# SCH_USB-hub_2025-08-26.net
KiCad netlist of a schematic drawn in EasyEDA
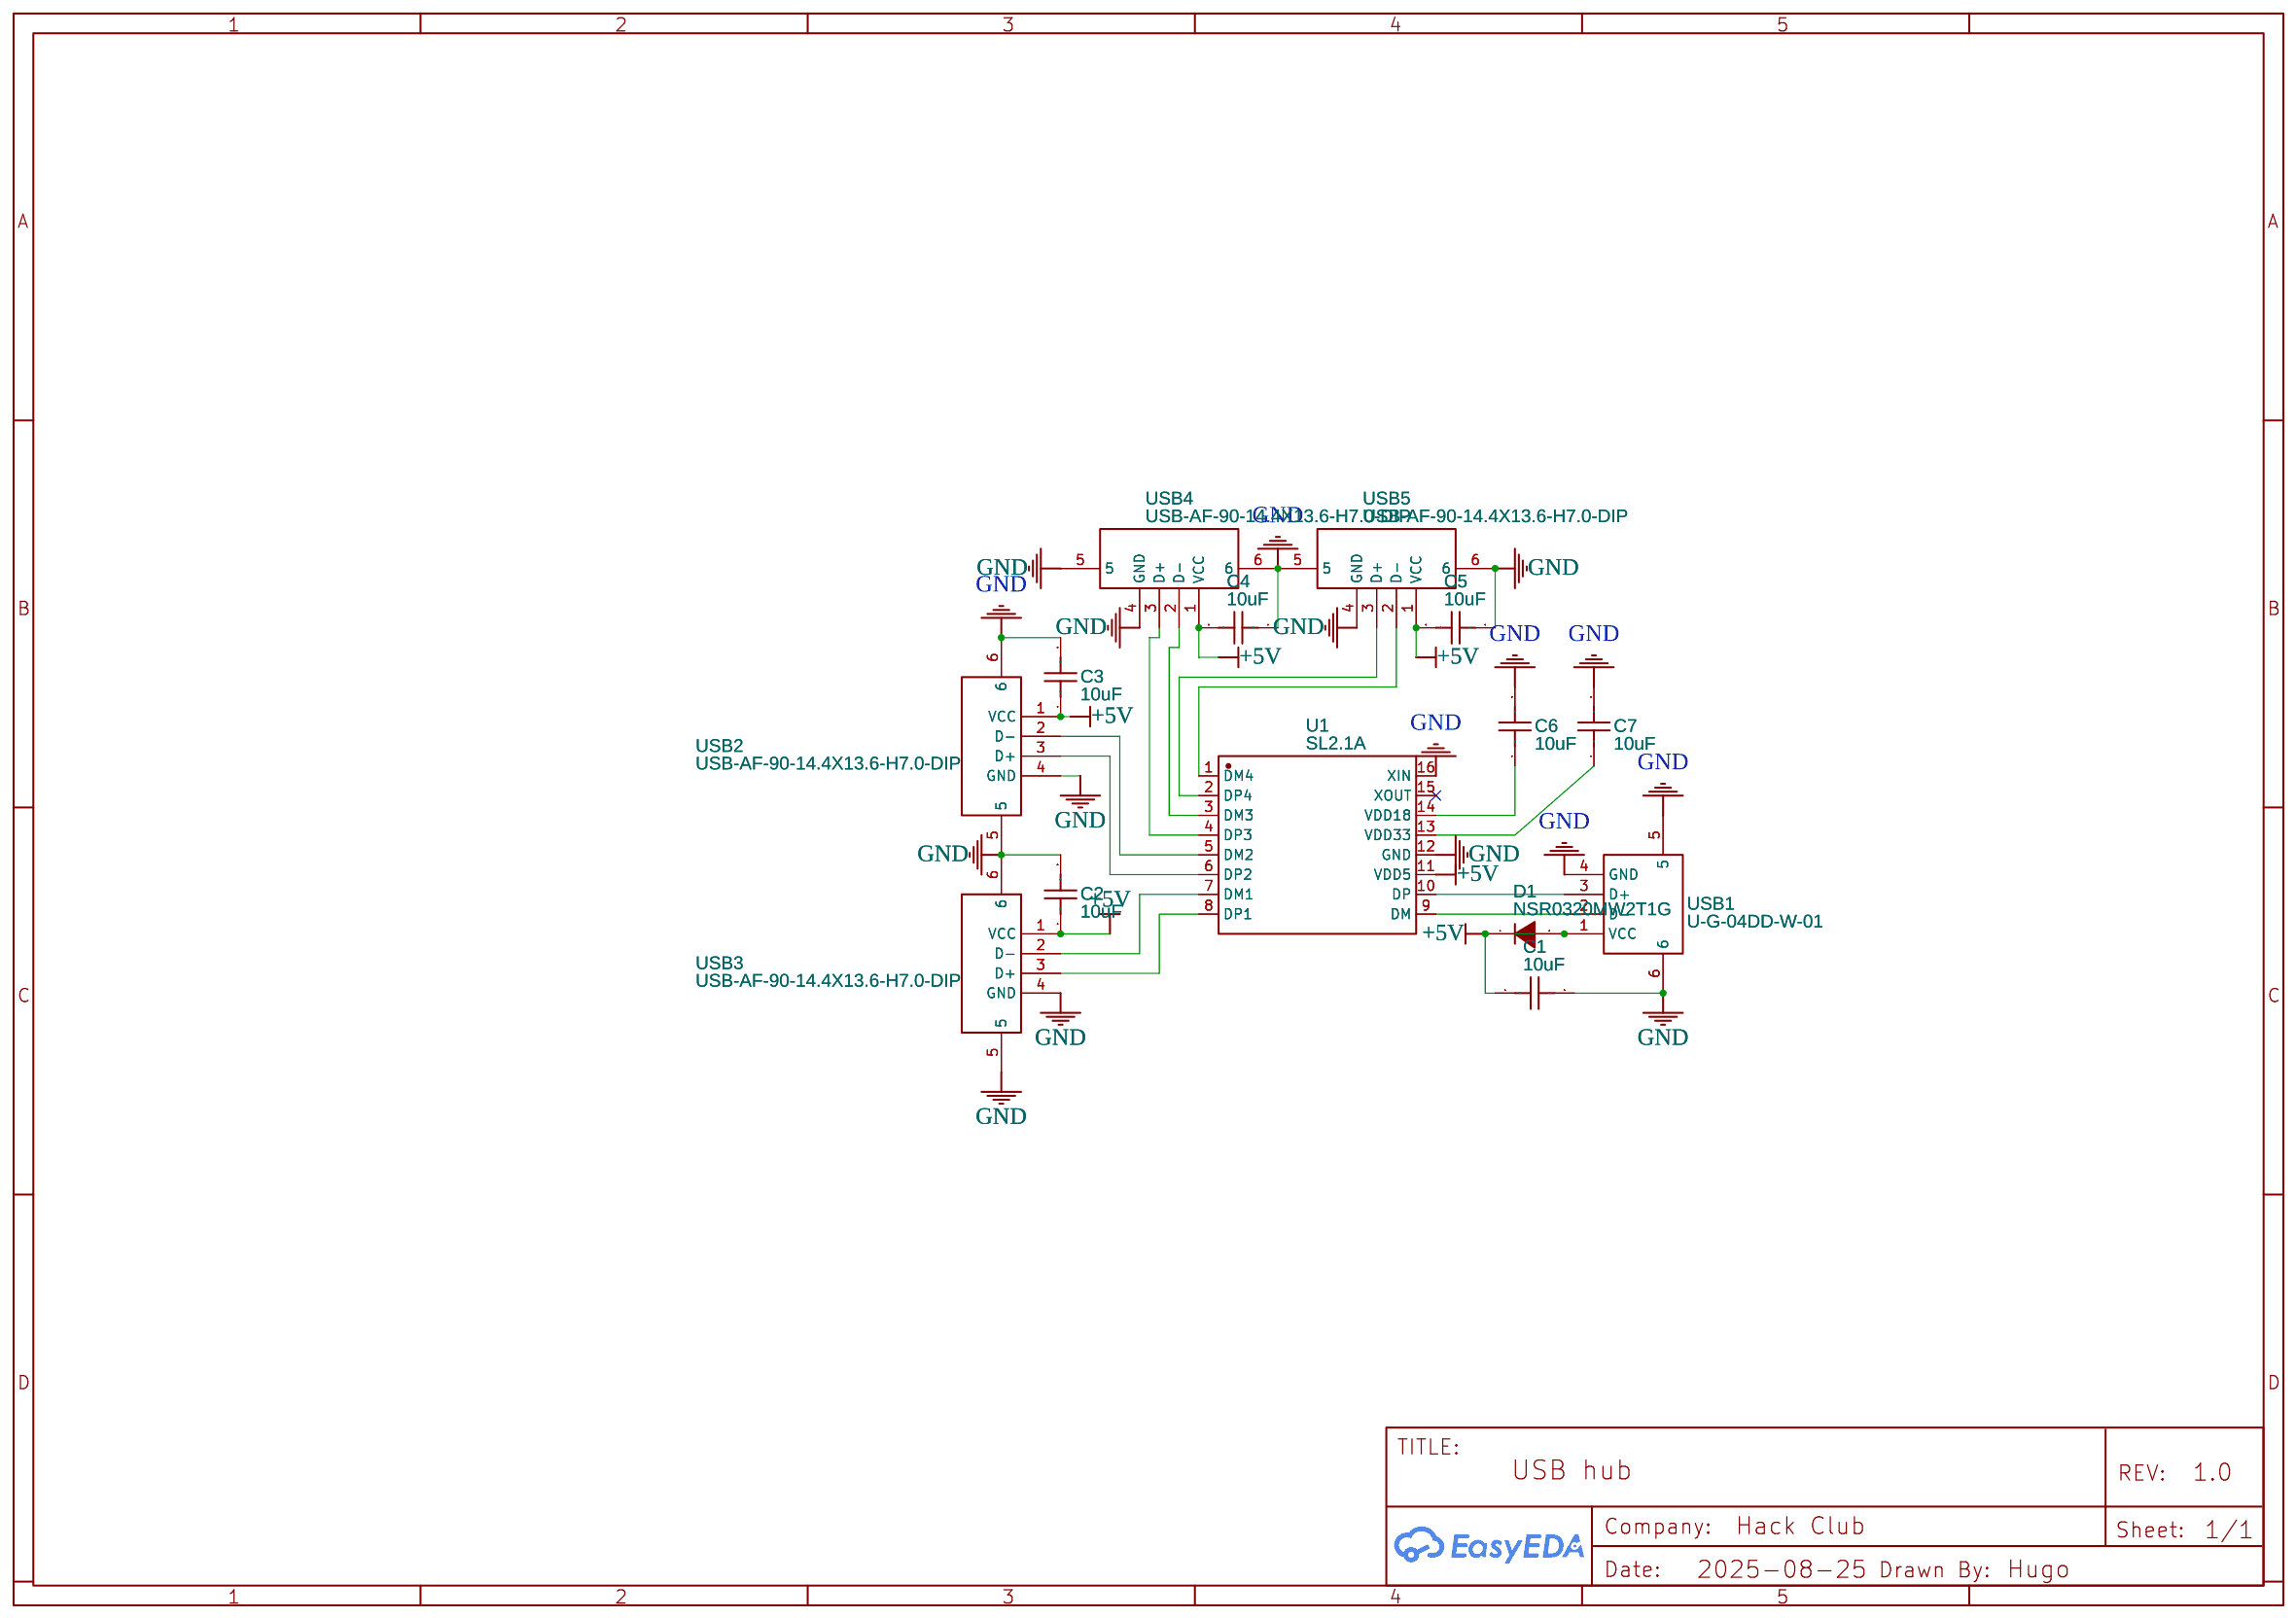
[diagram p0: schematic sheet]

(export (version "E")
  (design (tool "Eeschema 10.0.6"))
  (components
    (comp (ref "C1")
      (value "10uF")
      (fields
        (field (name "Manufacturer Part") "CL10A106KP8NNNC")
        (field (name "Manufacturer") "SAMSUNG(三星)")
      )
      (libsource (lib "") (part "CL10A106KP8NNNC_2"))
    )
    (comp (ref "C2")
      (value "10uF")
      (fields
        (field (name "Manufacturer Part") "CL10A106KP8NNNC")
        (field (name "Manufacturer") "SAMSUNG(三星)")
      )
      (libsource (lib "") (part "CL10A106KP8NNNC"))
    )
    (comp (ref "C3")
      (value "10uF")
      (fields
        (field (name "Manufacturer Part") "CL10A106KP8NNNC")
        (field (name "Manufacturer") "SAMSUNG(三星)")
      )
      (libsource (lib "") (part "CL10A106KP8NNNC"))
    )
    (comp (ref "C4")
      (value "10uF")
      (fields
        (field (name "Manufacturer Part") "CL10A106KP8NNNC")
        (field (name "Manufacturer") "SAMSUNG(三星)")
      )
      (libsource (lib "") (part "CL10A106KP8NNNC_1"))
    )
    (comp (ref "C5")
      (value "10uF")
      (fields
        (field (name "Manufacturer Part") "CL10A106KP8NNNC")
        (field (name "Manufacturer") "SAMSUNG(三星)")
      )
      (libsource (lib "") (part "CL10A106KP8NNNC_1"))
    )
    (comp (ref "C6")
      (value "10uF")
      (fields
        (field (name "Manufacturer Part") "CL10A106KP8NNNC")
        (field (name "Manufacturer") "SAMSUNG(三星)")
      )
      (libsource (lib "") (part "CL10A106KP8NNNC"))
    )
    (comp (ref "C7")
      (value "10uF")
      (fields
        (field (name "Manufacturer Part") "CL10A106KP8NNNC")
        (field (name "Manufacturer") "SAMSUNG(三星)")
      )
      (libsource (lib "") (part "CL10A106KP8NNNC"))
    )
    (comp (ref "D1")
      (value "NSR0320MW2T1G")
      (fields (field (name "Manufacturer") "onsemi(安森美)"))
      (libsource (lib "") (part "NSR0320MW2T1G"))
    )
    (comp (ref "U1")
      (value "SL2.1A")
      (fields (field (name "Manufacturer") "CoreChips(和芯润德)"))
      (libsource (lib "") (part "SL2.1A"))
    )
    (comp (ref "USB1")
      (value "U-G-04DD-W-01")
      (fields (field (name "Manufacturer Part") "U-G-O4DD-W-1") (field (name "Manufacturer") "韩国韩荣"))
      (libsource (lib "") (part "U-G-04DD-W-01"))
    )
    (comp (ref "USB2")
      (value "USB-AF-90-14.4X13.6-H7.0-DIP")
      (fields (field (name "Manufacturer Part") "903-131A1011D10100") (field (name "Manufacturer") "精拓金"))
      (libsource (lib "") (part "USB-AF-90-14.4X13.6-H7.0-DIP"))
    )
    (comp (ref "USB3")
      (value "USB-AF-90-14.4X13.6-H7.0-DIP")
      (fields (field (name "Manufacturer Part") "903-131A1011D10100") (field (name "Manufacturer") "精拓金"))
      (libsource (lib "") (part "USB-AF-90-14.4X13.6-H7.0-DIP"))
    )
    (comp (ref "USB4")
      (value "USB-AF-90-14.4X13.6-H7.0-DIP")
      (fields (field (name "Manufacturer Part") "903-131A1011D10100") (field (name "Manufacturer") "精拓金"))
      (libsource (lib "") (part "USB-AF-90-14.4X13.6-H7.0-DIP_1"))
    )
    (comp (ref "USB5")
      (value "USB-AF-90-14.4X13.6-H7.0-DIP")
      (fields (field (name "Manufacturer Part") "903-131A1011D10100") (field (name "Manufacturer") "精拓金"))
      (libsource (lib "") (part "USB-AF-90-14.4X13.6-H7.0-DIP_1"))
    )
  )
  (nets
    (net (code "1") (name "+5V") (class "Default")
      (node (ref "C1") (pin "1") (pinfunction "1_1") (pintype "unspecified"))
      (node (ref "C2") (pin "1") (pinfunction "1_1") (pintype "unspecified"))
      (node (ref "C3") (pin "1") (pinfunction "1_1") (pintype "unspecified"))
      (node (ref "C4") (pin "2") (pinfunction "2_2") (pintype "unspecified"))
      (node (ref "C5") (pin "2") (pinfunction "2_2") (pintype "unspecified"))
      (node (ref "D1") (pin "1") (pinfunction "C_1") (pintype "unspecified"))
      (node (ref "D1") (pin "2") (pinfunction "A_2") (pintype "unspecified"))
      (node (ref "U1") (pin "11") (pinfunction "VDD5_11") (pintype "unspecified"))
      (node (ref "USB1") (pin "1") (pinfunction "VCC_1") (pintype "unspecified"))
      (node (ref "USB2") (pin "1") (pinfunction "VCC_1") (pintype "unspecified"))
      (node (ref "USB3") (pin "1") (pinfunction "VCC_1") (pintype "unspecified"))
      (node (ref "USB4") (pin "1") (pinfunction "VCC_1") (pintype "unspecified"))
      (node (ref "USB5") (pin "1") (pinfunction "VCC_1") (pintype "unspecified"))
    )
    (net (code "2") (name "GND") (class "Default")
      (node (ref "C1") (pin "2") (pinfunction "2_2") (pintype "unspecified"))
      (node (ref "C2") (pin "2") (pinfunction "2_2") (pintype "unspecified"))
      (node (ref "C3") (pin "2") (pinfunction "2_2") (pintype "unspecified"))
      (node (ref "C4") (pin "1") (pinfunction "1_1") (pintype "unspecified"))
      (node (ref "C5") (pin "1") (pinfunction "1_1") (pintype "unspecified"))
      (node (ref "C6") (pin "2") (pinfunction "2_2") (pintype "unspecified"))
      (node (ref "C7") (pin "2") (pinfunction "2_2") (pintype "unspecified"))
      (node (ref "U1") (pin "12") (pinfunction "GND_12") (pintype "unspecified"))
      (node (ref "U1") (pin "16") (pinfunction "XIN_16") (pintype "unspecified"))
      (node (ref "USB1") (pin "4") (pinfunction "GND_4") (pintype "unspecified"))
      (node (ref "USB1") (pin "5") (pinfunction "5_5") (pintype "unspecified"))
      (node (ref "USB1") (pin "6") (pinfunction "6_6") (pintype "unspecified"))
      (node (ref "USB2") (pin "4") (pinfunction "GND_4") (pintype "unspecified"))
      (node (ref "USB2") (pin "5") (pinfunction "5_5") (pintype "unspecified"))
      (node (ref "USB2") (pin "6") (pinfunction "6_6") (pintype "unspecified"))
      (node (ref "USB3") (pin "4") (pinfunction "GND_4") (pintype "unspecified"))
      (node (ref "USB3") (pin "5") (pinfunction "5_5") (pintype "unspecified"))
      (node (ref "USB3") (pin "6") (pinfunction "6_6") (pintype "unspecified"))
      (node (ref "USB4") (pin "4") (pinfunction "GND_4") (pintype "unspecified"))
      (node (ref "USB4") (pin "5") (pinfunction "5_5") (pintype "unspecified"))
      (node (ref "USB4") (pin "6") (pinfunction "6_6") (pintype "unspecified"))
      (node (ref "USB5") (pin "4") (pinfunction "GND_4") (pintype "unspecified"))
      (node (ref "USB5") (pin "5") (pinfunction "5_5") (pintype "unspecified"))
      (node (ref "USB5") (pin "6") (pinfunction "6_6") (pintype "unspecified"))
    )
    (net (code "3") (name "Net-(U1-DM)") (class "Default")
      (node (ref "U1") (pin "9") (pinfunction "DM_9") (pintype "unspecified"))
      (node (ref "USB1") (pin "2") (pinfunction "D-_2") (pintype "unspecified"))
    )
    (net (code "4") (name "Net-(U1-DM1)") (class "Default")
      (node (ref "U1") (pin "7") (pinfunction "DM1_7") (pintype "unspecified"))
      (node (ref "USB3") (pin "2") (pinfunction "D-_2") (pintype "unspecified"))
    )
    (net (code "5") (name "Net-(U1-DM2)") (class "Default")
      (node (ref "U1") (pin "5") (pinfunction "DM2_5") (pintype "unspecified"))
      (node (ref "USB2") (pin "2") (pinfunction "D-_2") (pintype "unspecified"))
    )
    (net (code "6") (name "Net-(U1-DM3)") (class "Default")
      (node (ref "U1") (pin "3") (pinfunction "DM3_3") (pintype "unspecified"))
      (node (ref "USB4") (pin "2") (pinfunction "D-_2") (pintype "unspecified"))
    )
    (net (code "7") (name "Net-(U1-DM4)") (class "Default")
      (node (ref "U1") (pin "1") (pinfunction "DM4_1") (pintype "unspecified"))
      (node (ref "USB5") (pin "2") (pinfunction "D-_2") (pintype "unspecified"))
    )
    (net (code "8") (name "Net-(U1-DP)") (class "Default")
      (node (ref "U1") (pin "10") (pinfunction "DP_10") (pintype "unspecified"))
      (node (ref "USB1") (pin "3") (pinfunction "D+_3") (pintype "unspecified"))
    )
    (net (code "9") (name "Net-(U1-DP1)") (class "Default")
      (node (ref "U1") (pin "8") (pinfunction "DP1_8") (pintype "unspecified"))
      (node (ref "USB3") (pin "3") (pinfunction "D+_3") (pintype "unspecified"))
    )
    (net (code "10") (name "Net-(U1-DP2)") (class "Default")
      (node (ref "U1") (pin "6") (pinfunction "DP2_6") (pintype "unspecified"))
      (node (ref "USB2") (pin "3") (pinfunction "D+_3") (pintype "unspecified"))
    )
    (net (code "11") (name "Net-(U1-DP3)") (class "Default")
      (node (ref "U1") (pin "4") (pinfunction "DP3_4") (pintype "unspecified"))
      (node (ref "USB4") (pin "3") (pinfunction "D+_3") (pintype "unspecified"))
    )
    (net (code "12") (name "Net-(U1-DP4)") (class "Default")
      (node (ref "U1") (pin "2") (pinfunction "DP4_2") (pintype "unspecified"))
      (node (ref "USB5") (pin "3") (pinfunction "D+_3") (pintype "unspecified"))
    )
    (net (code "13") (name "Net-(U1-VDD18)") (class "Default")
      (node (ref "C6") (pin "1") (pinfunction "1_1") (pintype "unspecified"))
      (node (ref "U1") (pin "14") (pinfunction "VDD18_14") (pintype "unspecified"))
    )
    (net (code "14") (name "Net-(U1-VDD33)") (class "Default")
      (node (ref "C7") (pin "1") (pinfunction "1_1") (pintype "unspecified"))
      (node (ref "U1") (pin "13") (pinfunction "VDD33_13") (pintype "unspecified"))
    )
    (net (code "15") (name "unconnected-(U1-XOUT-Pad15)") (class "Default")
      (node (ref "U1") (pin "15") (pinfunction "XOUT_15") (pintype "unspecified+no_connect"))
    )
  )
)
